# design.net
KiCad netlist of a schematic drawn in Altium Designer
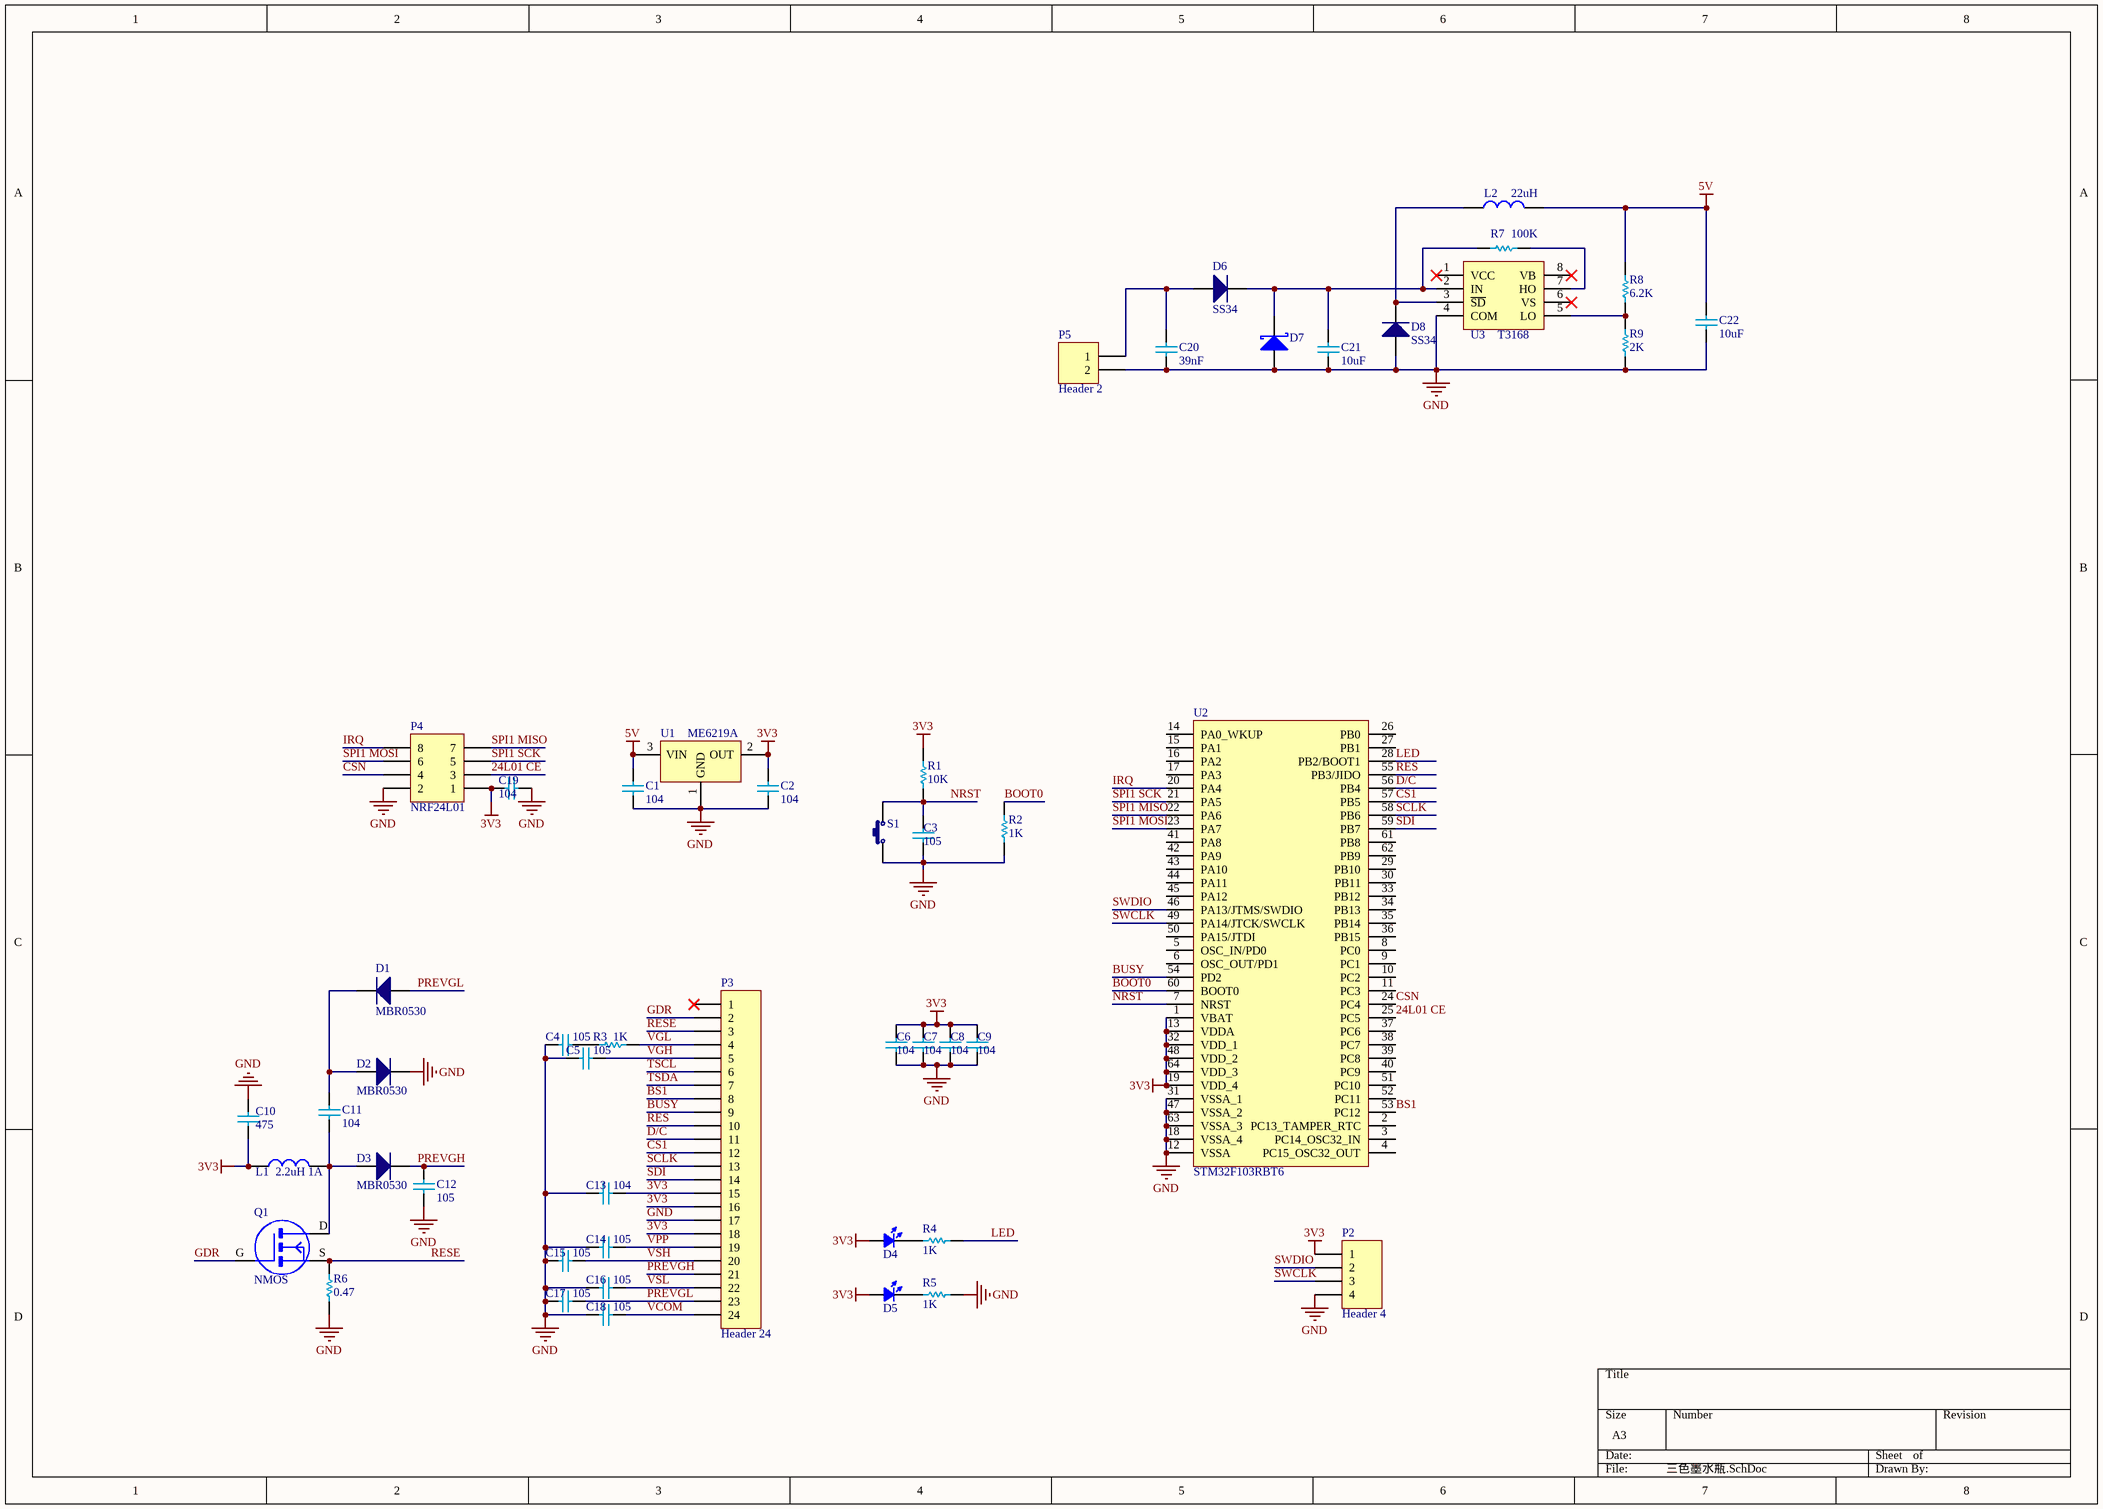
[diagram p0: 三色墨水瓶.SchDoc]

(export (version "E")
  (design (tool "Eeschema 10.0.6"))
  (components
    (comp (ref "C1")
      (value "104")
      (footprint "0805C")
      (fields (field (name "Comment") "CAP_1"))
      (libsource (lib "Xgui") (part "CAP_1"))
    )
    (comp (ref "C2")
      (value "104")
      (footprint "0805C")
      (fields (field (name "Comment") "CAP_1"))
      (libsource (lib "Xgui") (part "CAP_1"))
    )
    (comp (ref "C3")
      (value "105")
      (footprint "0805C")
      (fields (field (name "Comment") "CAP_1"))
      (libsource (lib "Xgui") (part "CAP_1"))
    )
    (comp (ref "C4")
      (value "105")
      (footprint "0805C")
      (fields (field (name "Comment") "CAP_1"))
      (libsource (lib "Xgui") (part "CAP_1"))
    )
    (comp (ref "C5")
      (value "105")
      (footprint "0805C")
      (fields (field (name "Comment") "CAP_1"))
      (libsource (lib "Xgui") (part "CAP_1"))
    )
    (comp (ref "C6")
      (value "104")
      (footprint "0805C")
      (fields (field (name "Comment") "CAP_1"))
      (libsource (lib "Xgui") (part "CAP_1"))
    )
    (comp (ref "C7")
      (value "104")
      (footprint "0805C")
      (fields (field (name "Comment") "CAP_1"))
      (libsource (lib "Xgui") (part "CAP_1"))
    )
    (comp (ref "C8")
      (value "104")
      (footprint "0805C")
      (fields (field (name "Comment") "CAP_1"))
      (libsource (lib "Xgui") (part "CAP_1"))
    )
    (comp (ref "C9")
      (value "104")
      (footprint "0805C")
      (fields (field (name "Comment") "CAP_1"))
      (libsource (lib "Xgui") (part "CAP_1"))
    )
    (comp (ref "C10")
      (value "475")
      (footprint "0805C")
      (fields (field (name "Comment") "CAP_1"))
      (libsource (lib "Xgui") (part "CAP_1"))
    )
    (comp (ref "C11")
      (value "104")
      (footprint "0805C")
      (fields (field (name "Comment") "CAP_1"))
      (libsource (lib "Xgui") (part "CAP_1"))
    )
    (comp (ref "C12")
      (value "105")
      (footprint "0805C")
      (fields (field (name "Comment") "CAP_1"))
      (libsource (lib "Xgui") (part "CAP_1"))
    )
    (comp (ref "C13")
      (value "104")
      (footprint "0805C")
      (fields (field (name "Comment") "CAP_1"))
      (libsource (lib "Xgui") (part "CAP_1"))
    )
    (comp (ref "C14")
      (value "105")
      (footprint "0805C")
      (fields (field (name "Comment") "CAP_1"))
      (libsource (lib "Xgui") (part "CAP_1"))
    )
    (comp (ref "C15")
      (value "105")
      (footprint "0805C")
      (fields (field (name "Comment") "CAP_1"))
      (libsource (lib "Xgui") (part "CAP_1"))
    )
    (comp (ref "C16")
      (value "105")
      (footprint "0805C")
      (fields (field (name "Comment") "CAP_1"))
      (libsource (lib "Xgui") (part "CAP_1"))
    )
    (comp (ref "C17")
      (value "105")
      (footprint "0805C")
      (fields (field (name "Comment") "CAP_1"))
      (libsource (lib "Xgui") (part "CAP_1"))
    )
    (comp (ref "C18")
      (value "105")
      (footprint "0805C")
      (fields (field (name "Comment") "CAP_1"))
      (libsource (lib "Xgui") (part "CAP_1"))
    )
    (comp (ref "C19")
      (value "104")
      (footprint "0805C")
      (fields (field (name "Comment") "CAP_1"))
      (libsource (lib "Xgui") (part "CAP_1"))
    )
    (comp (ref "C20")
      (value "39nF")
      (footprint "0805C")
      (fields (field (name "Comment") "CAP_1"))
      (libsource (lib "Xgui") (part "CAP_1"))
    )
    (comp (ref "C21")
      (value "10uF")
      (footprint "0805C")
      (fields (field (name "Comment") "CAP_1"))
      (libsource (lib "Xgui") (part "CAP_1"))
    )
    (comp (ref "C22")
      (value "10uF")
      (footprint "0805C")
      (fields (field (name "Comment") "CAP_1"))
      (libsource (lib "Xgui") (part "CAP_1"))
    )
    (comp (ref "D1")
      (value "MBR0530")
      (footprint "LC-SOD-123")
      (libsource (lib "Common Device") (part "Diode"))
    )
    (comp (ref "D2")
      (value "MBR0530")
      (footprint "LC-SOD-123")
      (libsource (lib "Common Device") (part "Diode"))
    )
    (comp (ref "D3")
      (value "MBR0530")
      (footprint "LC-SOD-123")
      (libsource (lib "Common Device") (part "Diode"))
    )
    (comp (ref "D4") (value "LED") (footprint "0805C") (libsource (lib "Xgui") (part "LED")))
    (comp (ref "D5") (value "LED") (footprint "0805C") (libsource (lib "Xgui") (part "LED")))
    (comp (ref "D6") (value "SS34") (footprint "DO-214AA") (libsource (lib "Common Device") (part "Diode")))
    (comp (ref "D7")
      (value "Diode Schottky")
      (footprint "0805R")
      (libsource (lib "Common Device") (part "Diode Schottky"))
    )
    (comp (ref "D8") (value "SS34") (footprint "DO-214AA") (libsource (lib "Common Device") (part "Diode")))
    (comp (ref "L1")
      (value "2.2uH 1A")
      (footprint "1210R")
      (libsource (lib "Common Device") (part "Inductor"))
    )
    (comp (ref "L2") (value "22uH") (footprint "R2512") (libsource (lib "Common Device") (part "Inductor")))
    (comp (ref "P2")
      (value "Header 4")
      (footprint "HDR1X4")
      (description "Header, 4-Pin")
      (fields (field (name "PUBLISHER") "Altium Limited"))
      (libsource (lib "Common Headers") (part "Header 4"))
    )
    (comp (ref "P3")
      (value "Header 24")
      (footprint "FPC 24P")
      (description "Header, 24-Pin")
      (fields (field (name "PUBLISHER") "Altium Limited"))
      (libsource (lib "Miscellaneous Connectors") (part "Header 24"))
    )
    (comp (ref "P4")
      (value "NRF24L01")
      (footprint "NRF24L01M")
      (description "Header, 4-Pin, Dual row")
      (fields (field (name "PUBLISHER") "Altium Limited"))
      (libsource (lib "Miscellaneous Connectors") (part "Header 4X2"))
    )
    (comp (ref "P5")
      (value "Header 2")
      (footprint "HDR1X2")
      (description "Header, 2-Pin")
      (fields (field (name "PUBLISHER") "Altium Limited"))
      (libsource (lib "Common Headers") (part "Header 2"))
    )
    (comp (ref "Q1") (value "NMOS") (footprint "SOT-23-MOS") (libsource (lib "Xgui") (part "NMOS")))
    (comp (ref "R1")
      (value "RES")
      (footprint "0805R")
      (fields (field (name "VALUES") "10K"))
      (libsource (lib "Xgui") (part "RES"))
    )
    (comp (ref "R2")
      (value "RES")
      (footprint "0805R")
      (fields (field (name "VALUES") "1K"))
      (libsource (lib "Xgui") (part "RES"))
    )
    (comp (ref "R3")
      (value "RES")
      (footprint "0805R")
      (fields (field (name "VALUES") "1K"))
      (libsource (lib "Xgui") (part "RES"))
    )
    (comp (ref "R4")
      (value "RES")
      (footprint "0805R")
      (fields (field (name "VALUES") "1K"))
      (libsource (lib "Xgui") (part "RES"))
    )
    (comp (ref "R5")
      (value "RES")
      (footprint "0805R")
      (fields (field (name "VALUES") "1K"))
      (libsource (lib "Xgui") (part "RES"))
    )
    (comp (ref "R6")
      (value "RES")
      (footprint "0805R")
      (fields (field (name "VALUES") "0.47"))
      (libsource (lib "Xgui") (part "RES"))
    )
    (comp (ref "R7")
      (value "RES")
      (footprint "0805R")
      (fields (field (name "VALUES") "100K"))
      (libsource (lib "Xgui") (part "RES"))
    )
    (comp (ref "R8")
      (value "RES")
      (footprint "0805R")
      (fields (field (name "VALUES") "6.2K"))
      (libsource (lib "Xgui") (part "RES"))
    )
    (comp (ref "R9")
      (value "RES")
      (footprint "0805R")
      (fields (field (name "VALUES") "2K"))
      (libsource (lib "Xgui") (part "RES"))
    )
    (comp (ref "S1")
      (value "Switch")
      (footprint "SW_PB2_A1")
      (libsource (lib "Common Device") (part "Switch"))
    )
    (comp (ref "U1")
      (value "ME6219A")
      (footprint "LC-SOT-23(SOT-23-3)")
      (libsource (lib "Xgui") (part "ME6219A"))
    )
    (comp (ref "U2")
      (value "STM32F103RBT6")
      (footprint "LQFP-64")
      (libsource (lib "Common Device") (part "STM32F103RBT6"))
    )
    (comp (ref "U3")
      (value "T3168")
      (footprint "SOIC-8")
      (description "IR2104")
      (libsource (lib "Xgui") (part "IR2104"))
    )
  )
  (nets
    (net (code "1") (name "/24L01 CE") (class "Default")
      (node (ref "P4") (pin "3") (pinfunction "3_3") (pintype "passive"))
      (node (ref "U2") (pin "25") (pinfunction "PC5_25") (pintype "passive"))
    )
    (net (code "2") (name "/BOOT0") (class "Default")
      (node (ref "R2") (pin "1") (pinfunction "1_1") (pintype "passive"))
      (node (ref "U2") (pin "60") (pinfunction "BOOT0_60") (pintype "passive"))
    )
    (net (code "3") (name "/BS1") (class "Default")
      (node (ref "P3") (pin "8") (pinfunction "8_8") (pintype "passive"))
      (node (ref "U2") (pin "53") (pinfunction "PC12_53") (pintype "passive"))
    )
    (net (code "4") (name "/BUSY") (class "Default")
      (node (ref "P3") (pin "9") (pinfunction "9_9") (pintype "passive"))
      (node (ref "U2") (pin "54") (pinfunction "PD2_54") (pintype "passive"))
    )
    (net (code "5") (name "/CS1") (class "Default")
      (node (ref "P3") (pin "12") (pinfunction "12_12") (pintype "passive"))
      (node (ref "U2") (pin "57") (pinfunction "PB5_57") (pintype "passive"))
    )
    (net (code "6") (name "/CSN") (class "Default")
      (node (ref "P4") (pin "4") (pinfunction "4_4") (pintype "passive"))
      (node (ref "U2") (pin "24") (pinfunction "PC4_24") (pintype "passive"))
    )
    (net (code "7") (name "/D{slash}C") (class "Default")
      (node (ref "P3") (pin "11") (pinfunction "11_11") (pintype "passive"))
      (node (ref "U2") (pin "56") (pinfunction "PB4_56") (pintype "passive"))
    )
    (net (code "8") (name "/GDR") (class "Default")
      (node (ref "P3") (pin "2") (pinfunction "2_2") (pintype "passive"))
      (node (ref "Q1") (pin "G") (pinfunction "G_G") (pintype "passive"))
    )
    (net (code "9") (name "/IRQ") (class "Default")
      (node (ref "P4") (pin "8") (pinfunction "8_8") (pintype "passive"))
      (node (ref "U2") (pin "20") (pinfunction "PA4_20") (pintype "passive"))
    )
    (net (code "10") (name "/LED") (class "Default")
      (node (ref "R4") (pin "2") (pinfunction "2_2") (pintype "passive"))
      (node (ref "U2") (pin "28") (pinfunction "PB2/BOOT1_28") (pintype "passive"))
    )
    (net (code "11") (name "/NRST") (class "Default")
      (node (ref "C3") (pin "1") (pinfunction "1_1") (pintype "passive"))
      (node (ref "R1") (pin "2") (pinfunction "2_2") (pintype "passive"))
      (node (ref "S1") (pin "2") (pinfunction "1_2") (pintype "passive"))
      (node (ref "U2") (pin "7") (pinfunction "NRST_7") (pintype "passive"))
    )
    (net (code "12") (name "/PREVGH") (class "Default")
      (node (ref "C12") (pin "2") (pinfunction "2_2") (pintype "passive"))
      (node (ref "D3") (pin "2") (pinfunction "1_2") (pintype "passive"))
      (node (ref "P3") (pin "21") (pinfunction "21_21") (pintype "passive"))
    )
    (net (code "13") (name "/PREVGL") (class "Default")
      (node (ref "C17") (pin "2") (pinfunction "2_2") (pintype "passive"))
      (node (ref "D1") (pin "1") (pinfunction "0_1") (pintype "passive"))
      (node (ref "P3") (pin "23") (pinfunction "23_23") (pintype "passive"))
    )
    (net (code "14") (name "/RES") (class "Default")
      (node (ref "P3") (pin "10") (pinfunction "10_10") (pintype "passive"))
      (node (ref "U2") (pin "55") (pinfunction "PB3/JIDO_55") (pintype "passive"))
    )
    (net (code "15") (name "/RESE") (class "Default")
      (node (ref "P3") (pin "3") (pinfunction "3_3") (pintype "passive"))
      (node (ref "Q1") (pin "S") (pinfunction "S_S") (pintype "passive"))
      (node (ref "R6") (pin "2") (pinfunction "2_2") (pintype "passive"))
    )
    (net (code "16") (name "/SCLK") (class "Default")
      (node (ref "P3") (pin "13") (pinfunction "13_13") (pintype "passive"))
      (node (ref "U2") (pin "58") (pinfunction "PB6_58") (pintype "passive"))
    )
    (net (code "17") (name "/SDI") (class "Default")
      (node (ref "P3") (pin "14") (pinfunction "14_14") (pintype "passive"))
      (node (ref "U2") (pin "59") (pinfunction "PB7_59") (pintype "passive"))
    )
    (net (code "18") (name "/SPI1 MISO") (class "Default")
      (node (ref "P4") (pin "7") (pinfunction "7_7") (pintype "passive"))
      (node (ref "U2") (pin "22") (pinfunction "PA6_22") (pintype "passive"))
    )
    (net (code "19") (name "/SPI1 MOSI") (class "Default")
      (node (ref "P4") (pin "6") (pinfunction "6_6") (pintype "passive"))
      (node (ref "U2") (pin "23") (pinfunction "PA7_23") (pintype "passive"))
    )
    (net (code "20") (name "/SPI1 SCK") (class "Default")
      (node (ref "P4") (pin "5") (pinfunction "5_5") (pintype "passive"))
      (node (ref "U2") (pin "21") (pinfunction "PA5_21") (pintype "passive"))
    )
    (net (code "21") (name "/SWCLK") (class "Default")
      (node (ref "P2") (pin "3") (pinfunction "3_3") (pintype "passive"))
      (node (ref "U2") (pin "49") (pinfunction "PA14/JTCK/SWCLK_49") (pintype "passive"))
    )
    (net (code "22") (name "/SWDIO") (class "Default")
      (node (ref "P2") (pin "2") (pinfunction "2_2") (pintype "passive"))
      (node (ref "U2") (pin "46") (pinfunction "PA13/JTMS/SWDIO_46") (pintype "passive"))
    )
    (net (code "23") (name "/TSCL") (class "Default")
      (node (ref "P3") (pin "6") (pinfunction "6_6") (pintype "passive"))
    )
    (net (code "24") (name "/TSDA") (class "Default")
      (node (ref "P3") (pin "7") (pinfunction "7_7") (pintype "passive"))
    )
    (net (code "25") (name "/VCOM") (class "Default")
      (node (ref "C18") (pin "2") (pinfunction "2_2") (pintype "passive"))
      (node (ref "P3") (pin "24") (pinfunction "24_24") (pintype "passive"))
    )
    (net (code "26") (name "/VGH") (class "Default")
      (node (ref "C5") (pin "2") (pinfunction "2_2") (pintype "passive"))
      (node (ref "P3") (pin "5") (pinfunction "5_5") (pintype "passive"))
    )
    (net (code "27") (name "/VGL") (class "Default")
      (node (ref "P3") (pin "4") (pinfunction "4_4") (pintype "passive"))
      (node (ref "R3") (pin "2") (pinfunction "2_2") (pintype "passive"))
    )
    (net (code "28") (name "/VPP") (class "Default")
      (node (ref "C14") (pin "2") (pinfunction "2_2") (pintype "passive"))
      (node (ref "P3") (pin "19") (pinfunction "19_19") (pintype "passive"))
    )
    (net (code "29") (name "/VSH") (class "Default")
      (node (ref "C15") (pin "2") (pinfunction "2_2") (pintype "passive"))
      (node (ref "P3") (pin "20") (pinfunction "20_20") (pintype "passive"))
    )
    (net (code "30") (name "/VSL") (class "Default")
      (node (ref "C16") (pin "2") (pinfunction "2_2") (pintype "passive"))
      (node (ref "P3") (pin "22") (pinfunction "22_22") (pintype "passive"))
    )
    (net (code "31") (name "3V3") (class "Default")
      (node (ref "C10") (pin "2") (pinfunction "2_2") (pintype "passive"))
      (node (ref "C13") (pin "2") (pinfunction "2_2") (pintype "passive"))
      (node (ref "C19") (pin "1") (pinfunction "1_1") (pintype "passive"))
      (node (ref "C2") (pin "2") (pinfunction "2_2") (pintype "passive"))
      (node (ref "C6") (pin "2") (pinfunction "2_2") (pintype "passive"))
      (node (ref "C7") (pin "2") (pinfunction "2_2") (pintype "passive"))
      (node (ref "C8") (pin "2") (pinfunction "2_2") (pintype "passive"))
      (node (ref "C9") (pin "2") (pinfunction "2_2") (pintype "passive"))
      (node (ref "D4") (pin "1") (pinfunction "A_1") (pintype "passive"))
      (node (ref "D5") (pin "1") (pinfunction "A_1") (pintype "passive"))
      (node (ref "L1") (pin "1") (pinfunction "1_1") (pintype "passive"))
      (node (ref "P2") (pin "1") (pinfunction "1_1") (pintype "passive"))
      (node (ref "P3") (pin "15") (pinfunction "15_15") (pintype "passive"))
      (node (ref "P3") (pin "16") (pinfunction "16_16") (pintype "passive"))
      (node (ref "P3") (pin "18") (pinfunction "18_18") (pintype "passive"))
      (node (ref "P4") (pin "1") (pinfunction "1_1") (pintype "passive"))
      (node (ref "R1") (pin "1") (pinfunction "1_1") (pintype "passive"))
      (node (ref "U1") (pin "2") (pinfunction "OUT_2") (pintype "passive"))
      (node (ref "U2") (pin "1") (pinfunction "VBAT_1") (pintype "passive"))
      (node (ref "U2") (pin "13") (pinfunction "VDDA_13") (pintype "passive"))
      (node (ref "U2") (pin "19") (pinfunction "VDD_4_19") (pintype "passive"))
      (node (ref "U2") (pin "32") (pinfunction "VDD_1_32") (pintype "passive"))
      (node (ref "U2") (pin "48") (pinfunction "VDD_2_48") (pintype "passive"))
      (node (ref "U2") (pin "64") (pinfunction "VDD_3_64") (pintype "passive"))
    )
    (net (code "32") (name "5V") (class "Default")
      (node (ref "C1") (pin "2") (pinfunction "2_2") (pintype "passive"))
      (node (ref "C22") (pin "2") (pinfunction "2_2") (pintype "passive"))
      (node (ref "L2") (pin "2") (pinfunction "2_2") (pintype "passive"))
      (node (ref "R8") (pin "2") (pinfunction "2_2") (pintype "passive"))
      (node (ref "U1") (pin "3") (pinfunction "VIN_3") (pintype "passive"))
    )
    (net (code "33") (name "GND") (class "Default")
      (node (ref "C1") (pin "1") (pinfunction "1_1") (pintype "passive"))
      (node (ref "C10") (pin "1") (pinfunction "1_1") (pintype "passive"))
      (node (ref "C12") (pin "1") (pinfunction "1_1") (pintype "passive"))
      (node (ref "C13") (pin "1") (pinfunction "1_1") (pintype "passive"))
      (node (ref "C14") (pin "1") (pinfunction "1_1") (pintype "passive"))
      (node (ref "C15") (pin "1") (pinfunction "1_1") (pintype "passive"))
      (node (ref "C16") (pin "1") (pinfunction "1_1") (pintype "passive"))
      (node (ref "C17") (pin "1") (pinfunction "1_1") (pintype "passive"))
      (node (ref "C18") (pin "1") (pinfunction "1_1") (pintype "passive"))
      (node (ref "C19") (pin "2") (pinfunction "2_2") (pintype "passive"))
      (node (ref "C2") (pin "1") (pinfunction "1_1") (pintype "passive"))
      (node (ref "C20") (pin "1") (pinfunction "1_1") (pintype "passive"))
      (node (ref "C21") (pin "1") (pinfunction "1_1") (pintype "passive"))
      (node (ref "C22") (pin "1") (pinfunction "1_1") (pintype "passive"))
      (node (ref "C3") (pin "2") (pinfunction "2_2") (pintype "passive"))
      (node (ref "C4") (pin "1") (pinfunction "1_1") (pintype "passive"))
      (node (ref "C5") (pin "1") (pinfunction "1_1") (pintype "passive"))
      (node (ref "C6") (pin "1") (pinfunction "1_1") (pintype "passive"))
      (node (ref "C7") (pin "1") (pinfunction "1_1") (pintype "passive"))
      (node (ref "C8") (pin "1") (pinfunction "1_1") (pintype "passive"))
      (node (ref "C9") (pin "1") (pinfunction "1_1") (pintype "passive"))
      (node (ref "D2") (pin "2") (pinfunction "1_2") (pintype "passive"))
      (node (ref "D7") (pin "1") (pinfunction "A_1") (pintype "passive"))
      (node (ref "D8") (pin "1") (pinfunction "0_1") (pintype "passive"))
      (node (ref "P2") (pin "4") (pinfunction "4_4") (pintype "passive"))
      (node (ref "P3") (pin "17") (pinfunction "17_17") (pintype "passive"))
      (node (ref "P4") (pin "2") (pinfunction "2_2") (pintype "passive"))
      (node (ref "P5") (pin "2") (pinfunction "2_2") (pintype "passive"))
      (node (ref "R2") (pin "2") (pinfunction "2_2") (pintype "passive"))
      (node (ref "R5") (pin "2") (pinfunction "2_2") (pintype "passive"))
      (node (ref "R6") (pin "1") (pinfunction "1_1") (pintype "passive"))
      (node (ref "R9") (pin "1") (pinfunction "1_1") (pintype "passive"))
      (node (ref "S1") (pin "1") (pinfunction "0_1") (pintype "passive"))
      (node (ref "U1") (pin "1") (pinfunction "GND_1") (pintype "passive"))
      (node (ref "U2") (pin "12") (pinfunction "VSSA_12") (pintype "passive"))
      (node (ref "U2") (pin "18") (pinfunction "VSSA_4_18") (pintype "passive"))
      (node (ref "U2") (pin "31") (pinfunction "VSSA_1_31") (pintype "passive"))
      (node (ref "U2") (pin "47") (pinfunction "VSSA_2_47") (pintype "passive"))
      (node (ref "U2") (pin "63") (pinfunction "VSSA_3_63") (pintype "passive"))
      (node (ref "U3") (pin "4") (pinfunction "COM_4") (pintype "passive"))
    )
    (net (code "34") (name "Net-(C4-Pad2)") (class "Default")
      (node (ref "C4") (pin "2") (pinfunction "2_2") (pintype "passive"))
      (node (ref "R3") (pin "1") (pinfunction "1_1") (pintype "passive"))
    )
    (net (code "35") (name "Net-(D1-1)") (class "Default")
      (node (ref "C11") (pin "2") (pinfunction "2_2") (pintype "passive"))
      (node (ref "D1") (pin "2") (pinfunction "1_2") (pintype "passive"))
      (node (ref "D2") (pin "1") (pinfunction "0_1") (pintype "passive"))
    )
    (net (code "36") (name "Net-(D3-0)") (class "Default")
      (node (ref "C11") (pin "1") (pinfunction "1_1") (pintype "passive"))
      (node (ref "D3") (pin "1") (pinfunction "0_1") (pintype "passive"))
      (node (ref "L1") (pin "2") (pinfunction "2_2") (pintype "passive"))
      (node (ref "Q1") (pin "D") (pinfunction "D_D") (pintype "passive"))
    )
    (net (code "37") (name "Net-(D4-K)") (class "Default")
      (node (ref "D4") (pin "2") (pinfunction "K_2") (pintype "passive"))
      (node (ref "R4") (pin "1") (pinfunction "1_1") (pintype "passive"))
    )
    (net (code "38") (name "Net-(D5-K)") (class "Default")
      (node (ref "D5") (pin "2") (pinfunction "K_2") (pintype "passive"))
      (node (ref "R5") (pin "1") (pinfunction "1_1") (pintype "passive"))
    )
    (net (code "39") (name "Net-(D6-0)") (class "Default")
      (node (ref "C20") (pin "2") (pinfunction "2_2") (pintype "passive"))
      (node (ref "D6") (pin "1") (pinfunction "0_1") (pintype "passive"))
      (node (ref "P5") (pin "1") (pinfunction "1_1") (pintype "passive"))
    )
    (net (code "40") (name "Net-(D6-1)") (class "Default")
      (node (ref "C21") (pin "2") (pinfunction "2_2") (pintype "passive"))
      (node (ref "D6") (pin "2") (pinfunction "1_2") (pintype "passive"))
      (node (ref "D7") (pin "2") (pinfunction "K_2") (pintype "passive"))
      (node (ref "R7") (pin "1") (pinfunction "1_1") (pintype "passive"))
      (node (ref "U3") (pin "2") (pinfunction "IN_2") (pintype "passive"))
    )
    (net (code "41") (name "Net-(D8-1)") (class "Default")
      (node (ref "D8") (pin "2") (pinfunction "1_2") (pintype "passive"))
      (node (ref "L2") (pin "1") (pinfunction "1_1") (pintype "passive"))
      (node (ref "U3") (pin "3") (pinfunction "~{SD}_3") (pintype "passive"))
    )
    (net (code "42") (name "Net-(U3-HO)") (class "Default")
      (node (ref "R7") (pin "2") (pinfunction "2_2") (pintype "passive"))
      (node (ref "U3") (pin "7") (pinfunction "HO_7") (pintype "passive"))
    )
    (net (code "43") (name "Net-(U3-LO)") (class "Default")
      (node (ref "R8") (pin "1") (pinfunction "1_1") (pintype "passive"))
      (node (ref "R9") (pin "2") (pinfunction "2_2") (pintype "passive"))
      (node (ref "U3") (pin "5") (pinfunction "LO_5") (pintype "passive"))
    )
    (net (code "44") (name "unconnected-(P3-Pad1)") (class "Default")
      (node (ref "P3") (pin "1") (pinfunction "1_1") (pintype "passive+no_connect"))
    )
    (net (code "45") (name "unconnected-(U2-OSC_IN{slash}PD0-Pad5)") (class "Default")
      (node (ref "U2") (pin "5") (pinfunction "OSC_IN/PD0_5") (pintype "passive"))
    )
    (net (code "46") (name "unconnected-(U2-OSC_OUT{slash}PD1-Pad6)") (class "Default")
      (node (ref "U2") (pin "6") (pinfunction "OSC_OUT/PD1_6") (pintype "passive"))
    )
    (net (code "47") (name "unconnected-(U2-PA0_WKUP-Pad14)") (class "Default")
      (node (ref "U2") (pin "14") (pinfunction "PA0_WKUP_14") (pintype "passive"))
    )
    (net (code "48") (name "unconnected-(U2-PA1-Pad15)") (class "Default")
      (node (ref "U2") (pin "15") (pinfunction "PA1_15") (pintype "passive"))
    )
    (net (code "49") (name "unconnected-(U2-PA2-Pad16)") (class "Default")
      (node (ref "U2") (pin "16") (pinfunction "PA2_16") (pintype "passive"))
    )
    (net (code "50") (name "unconnected-(U2-PA3-Pad17)") (class "Default")
      (node (ref "U2") (pin "17") (pinfunction "PA3_17") (pintype "passive"))
    )
    (net (code "51") (name "unconnected-(U2-PA8-Pad41)") (class "Default")
      (node (ref "U2") (pin "41") (pinfunction "PA8_41") (pintype "passive"))
    )
    (net (code "52") (name "unconnected-(U2-PA9-Pad42)") (class "Default")
      (node (ref "U2") (pin "42") (pinfunction "PA9_42") (pintype "passive"))
    )
    (net (code "53") (name "unconnected-(U2-PA10-Pad43)") (class "Default")
      (node (ref "U2") (pin "43") (pinfunction "PA10_43") (pintype "passive"))
    )
    (net (code "54") (name "unconnected-(U2-PA11-Pad44)") (class "Default")
      (node (ref "U2") (pin "44") (pinfunction "PA11_44") (pintype "passive"))
    )
    (net (code "55") (name "unconnected-(U2-PA12-Pad45)") (class "Default")
      (node (ref "U2") (pin "45") (pinfunction "PA12_45") (pintype "passive"))
    )
    (net (code "56") (name "unconnected-(U2-PA15{slash}JTDI-Pad50)") (class "Default")
      (node (ref "U2") (pin "50") (pinfunction "PA15/JTDI_50") (pintype "passive"))
    )
    (net (code "57") (name "unconnected-(U2-PB0-Pad26)") (class "Default")
      (node (ref "U2") (pin "26") (pinfunction "PB0_26") (pintype "passive"))
    )
    (net (code "58") (name "unconnected-(U2-PB1-Pad27)") (class "Default")
      (node (ref "U2") (pin "27") (pinfunction "PB1_27") (pintype "passive"))
    )
    (net (code "59") (name "unconnected-(U2-PB8-Pad61)") (class "Default")
      (node (ref "U2") (pin "61") (pinfunction "PB8_61") (pintype "passive"))
    )
    (net (code "60") (name "unconnected-(U2-PB9-Pad62)") (class "Default")
      (node (ref "U2") (pin "62") (pinfunction "PB9_62") (pintype "passive"))
    )
    (net (code "61") (name "unconnected-(U2-PB10-Pad29)") (class "Default")
      (node (ref "U2") (pin "29") (pinfunction "PB10_29") (pintype "passive"))
    )
    (net (code "62") (name "unconnected-(U2-PB11-Pad30)") (class "Default")
      (node (ref "U2") (pin "30") (pinfunction "PB11_30") (pintype "passive"))
    )
    (net (code "63") (name "unconnected-(U2-PB12-Pad33)") (class "Default")
      (node (ref "U2") (pin "33") (pinfunction "PB12_33") (pintype "passive"))
    )
    (net (code "64") (name "unconnected-(U2-PB13-Pad34)") (class "Default")
      (node (ref "U2") (pin "34") (pinfunction "PB13_34") (pintype "passive"))
    )
    (net (code "65") (name "unconnected-(U2-PB14-Pad35)") (class "Default")
      (node (ref "U2") (pin "35") (pinfunction "PB14_35") (pintype "passive"))
    )
    (net (code "66") (name "unconnected-(U2-PB15-Pad36)") (class "Default")
      (node (ref "U2") (pin "36") (pinfunction "PB15_36") (pintype "passive"))
    )
    (net (code "67") (name "unconnected-(U2-PC0-Pad8)") (class "Default")
      (node (ref "U2") (pin "8") (pinfunction "PC0_8") (pintype "passive"))
    )
    (net (code "68") (name "unconnected-(U2-PC1-Pad9)") (class "Default")
      (node (ref "U2") (pin "9") (pinfunction "PC1_9") (pintype "passive"))
    )
    (net (code "69") (name "unconnected-(U2-PC2-Pad10)") (class "Default")
      (node (ref "U2") (pin "10") (pinfunction "PC2_10") (pintype "passive"))
    )
    (net (code "70") (name "unconnected-(U2-PC3-Pad11)") (class "Default")
      (node (ref "U2") (pin "11") (pinfunction "PC3_11") (pintype "passive"))
    )
    (net (code "71") (name "unconnected-(U2-PC6-Pad37)") (class "Default")
      (node (ref "U2") (pin "37") (pinfunction "PC6_37") (pintype "passive"))
    )
    (net (code "72") (name "unconnected-(U2-PC7-Pad38)") (class "Default")
      (node (ref "U2") (pin "38") (pinfunction "PC7_38") (pintype "passive"))
    )
    (net (code "73") (name "unconnected-(U2-PC8-Pad39)") (class "Default")
      (node (ref "U2") (pin "39") (pinfunction "PC8_39") (pintype "passive"))
    )
    (net (code "74") (name "unconnected-(U2-PC9-Pad40)") (class "Default")
      (node (ref "U2") (pin "40") (pinfunction "PC9_40") (pintype "passive"))
    )
    (net (code "75") (name "unconnected-(U2-PC10-Pad51)") (class "Default")
      (node (ref "U2") (pin "51") (pinfunction "PC10_51") (pintype "passive"))
    )
    (net (code "76") (name "unconnected-(U2-PC11-Pad52)") (class "Default")
      (node (ref "U2") (pin "52") (pinfunction "PC11_52") (pintype "passive"))
    )
    (net (code "77") (name "unconnected-(U2-PC13_TAMPER_RTC-Pad2)") (class "Default")
      (node (ref "U2") (pin "2") (pinfunction "PC13_TAMPER_RTC_2") (pintype "passive"))
    )
    (net (code "78") (name "unconnected-(U2-PC14_OSC32_IN-Pad3)") (class "Default")
      (node (ref "U2") (pin "3") (pinfunction "PC14_OSC32_IN_3") (pintype "passive"))
    )
    (net (code "79") (name "unconnected-(U2-PC15_OSC32_OUT-Pad4)") (class "Default")
      (node (ref "U2") (pin "4") (pinfunction "PC15_OSC32_OUT_4") (pintype "passive"))
    )
    (net (code "80") (name "unconnected-(U3-VB-Pad8)") (class "Default")
      (node (ref "U3") (pin "8") (pinfunction "VB_8") (pintype "passive+no_connect"))
    )
    (net (code "81") (name "unconnected-(U3-VCC-Pad1)") (class "Default")
      (node (ref "U3") (pin "1") (pinfunction "VCC_1") (pintype "passive+no_connect"))
    )
    (net (code "82") (name "unconnected-(U3-VS-Pad6)") (class "Default")
      (node (ref "U3") (pin "6") (pinfunction "VS_6") (pintype "passive+no_connect"))
    )
  )
)
